# Shield.net
KiCad netlist of a schematic drawn in EAGLE
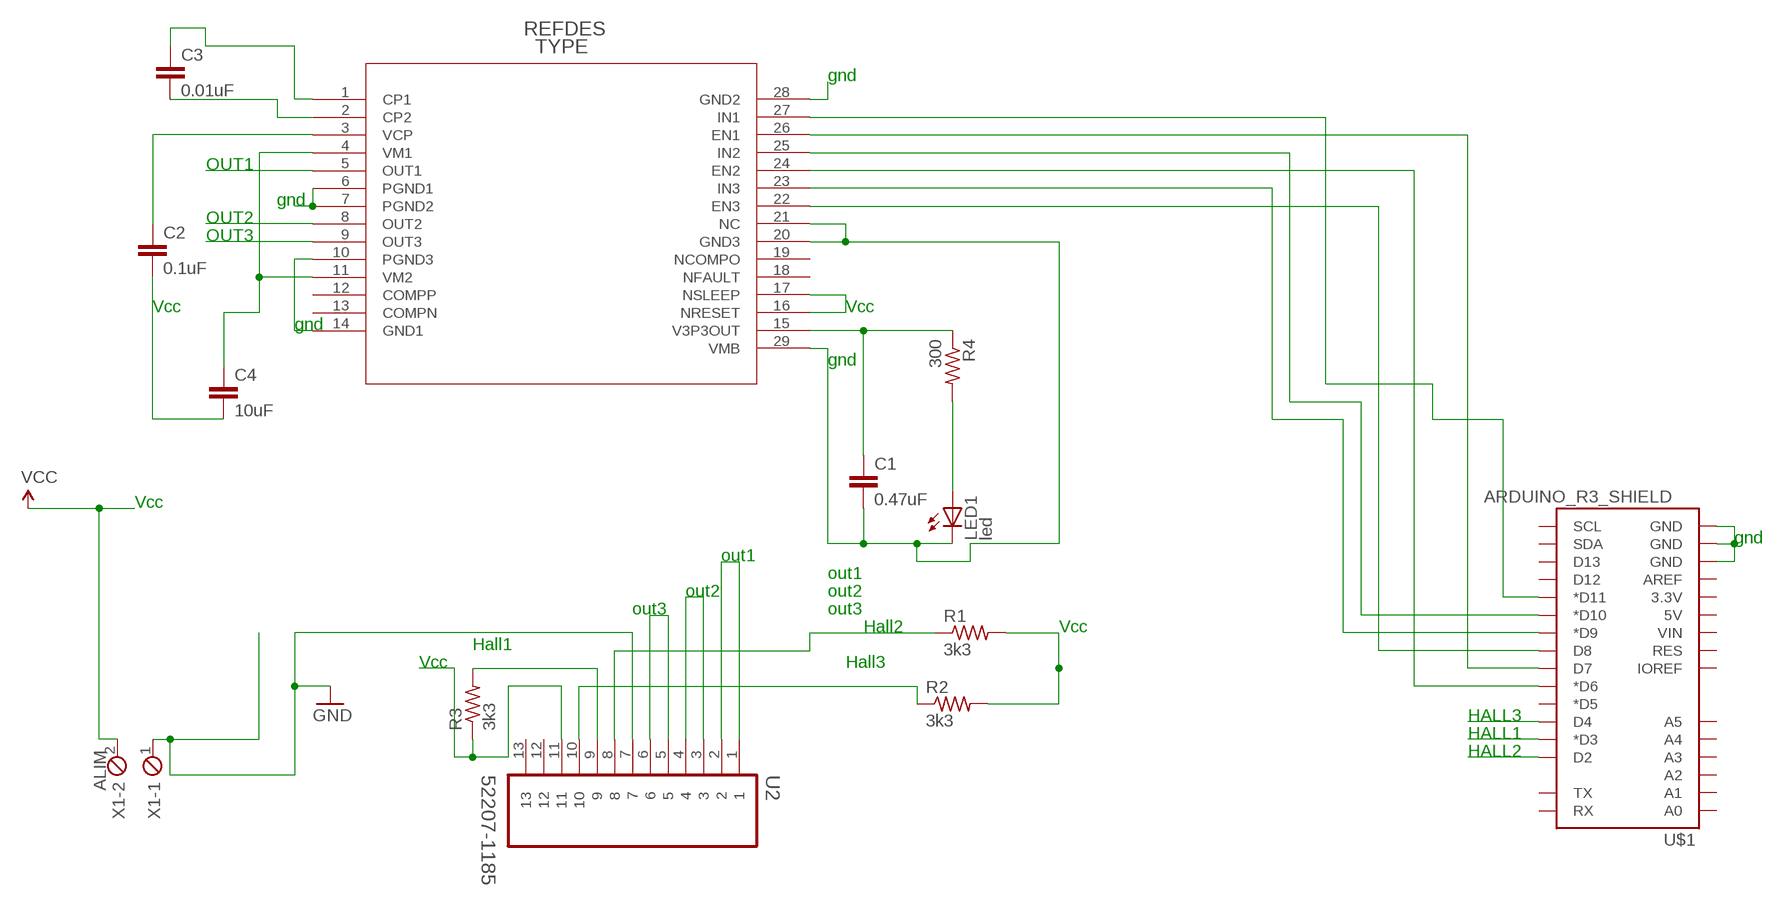
[diagram p0: schematic, sheet 1]

(export (version "E")
  (design (tool "Eeschema 10.0.6"))
  (components
    (comp (ref "C1")
      (value "0.47uF")
      (footprint "eagle-import:C025-025X050")
      (libsource (lib "eagle-import") (part "C-EU025-025X050"))
    )
    (comp (ref "C2")
      (value "0.1uF")
      (footprint "eagle-import:C102-043X133")
      (libsource (lib "eagle-import") (part "C-EU102-043X133"))
    )
    (comp (ref "C3")
      (value "0.01uF")
      (footprint "eagle-import:C025-025X050")
      (libsource (lib "eagle-import") (part "C-EU025-025X050"))
    )
    (comp (ref "C4")
      (value "10uF")
      (footprint "eagle-import:C025-050X050")
      (libsource (lib "eagle-import") (part "C-EU025-050X050"))
    )
    (comp (ref "LED1")
      (value "led")
      (footprint "eagle-import:LED3MM")
      (libsource (lib "eagle-import") (part "LED3MM"))
    )
    (comp (ref "R1")
      (value "3k3")
      (footprint "eagle-import:0207_10")
      (libsource (lib "eagle-import") (part "R-US_0207/10"))
    )
    (comp (ref "R2")
      (value "3k3")
      (footprint "eagle-import:0207_10")
      (libsource (lib "eagle-import") (part "R-US_0207/10"))
    )
    (comp (ref "R3")
      (value "3k3")
      (footprint "eagle-import:0207_10")
      (libsource (lib "eagle-import") (part "R-US_0207/10"))
    )
    (comp (ref "R4")
      (value "300")
      (footprint "eagle-import:0207_10")
      (libsource (lib "eagle-import") (part "R-US_0207/10"))
    )
    (comp (ref "U$1")
      (value "ARDUINO_R3_SHIELD")
      (footprint "eagle-import:UNO_R3_SHIELD")
      (libsource (lib "eagle-import") (part "ARDUINO_R3_SHIELD"))
    )
    (comp (ref "U1")
      (value "DRV8811_PWP_28")
      (footprint "eagle-import:PWP28_5P18X3P1")
      (libsource (lib "eagle-import") (part "DRV8811_PWP_28"))
    )
    (comp (ref "U2")
      (value "52207-1185")
      (footprint "eagle-import:MOLEX_52207-1185")
      (fields (field (name "MPN") "52207-1085"))
      (libsource (lib "eagle-import") (part "52207-1185"))
    )
    (comp (ref "X1")
      (value "ALIM")
      (footprint "eagle-import:2POL254")
      (libsource (lib "eagle-import") (part "MPT2"))
    )
  )
  (nets
    (net (code "1") (name "/HALL1") (class "Default")
      (node (ref "R3") (pin "2") (pinfunction "2_2") (pintype "passive"))
      (node (ref "U$1") (pin "D3") (pinfunction "*D3_D3") (pintype "bidirectional"))
      (node (ref "U2") (pin "9") (pinfunction "9_9") (pintype "passive"))
    )
    (net (code "2") (name "/HALL2") (class "Default")
      (node (ref "R1") (pin "1") (pinfunction "1_1") (pintype "passive"))
      (node (ref "U$1") (pin "D2") (pinfunction "D2_D2") (pintype "bidirectional"))
      (node (ref "U2") (pin "8") (pinfunction "8_8") (pintype "passive"))
    )
    (net (code "3") (name "/HALL3") (class "Default")
      (node (ref "R2") (pin "1") (pinfunction "1_1") (pintype "passive"))
      (node (ref "U$1") (pin "D4") (pinfunction "D4_D4") (pintype "bidirectional"))
      (node (ref "U2") (pin "10") (pinfunction "10_10") (pintype "passive"))
    )
    (net (code "4") (name "/OUT1") (class "Default")
      (node (ref "U1") (pin "5") (pinfunction "OUT1_5") (pintype "passive"))
      (node (ref "U2") (pin "1") (pinfunction "1_1") (pintype "passive"))
      (node (ref "U2") (pin "2") (pinfunction "2_2") (pintype "passive"))
    )
    (net (code "5") (name "/OUT2") (class "Default")
      (node (ref "U1") (pin "8") (pinfunction "OUT2_8") (pintype "passive"))
      (node (ref "U2") (pin "3") (pinfunction "3_3") (pintype "passive"))
      (node (ref "U2") (pin "4") (pinfunction "4_4") (pintype "passive"))
    )
    (net (code "6") (name "/OUT3") (class "Default")
      (node (ref "U1") (pin "9") (pinfunction "OUT3_9") (pintype "passive"))
      (node (ref "U2") (pin "5") (pinfunction "5_5") (pintype "passive"))
      (node (ref "U2") (pin "6") (pinfunction "6_6") (pintype "passive"))
    )
    (net (code "7") (name "GND") (class "Default")
      (node (ref "C1") (pin "2") (pinfunction "2_2") (pintype "passive"))
      (node (ref "LED1") (pin "K") (pinfunction "C_K") (pintype "passive"))
      (node (ref "U$1") (pin "GND@0") (pinfunction "GND_GND@0") (pintype "bidirectional"))
      (node (ref "U$1") (pin "GND@1") (pinfunction "GND_GND@1") (pintype "bidirectional"))
      (node (ref "U$1") (pin "GND@2") (pinfunction "GND_GND@2") (pintype "bidirectional"))
      (node (ref "U1") (pin "10") (pinfunction "PGND3_10") (pintype "passive"))
      (node (ref "U1") (pin "14") (pinfunction "GND1_14") (pintype "passive"))
      (node (ref "U1") (pin "20") (pinfunction "GND3_20") (pintype "passive"))
      (node (ref "U1") (pin "21") (pinfunction "NC_21") (pintype "passive"))
      (node (ref "U1") (pin "28") (pinfunction "GND2_28") (pintype "passive"))
      (node (ref "U1") (pin "29") (pinfunction "VMB_29") (pintype "passive"))
      (node (ref "U1") (pin "6") (pinfunction "PGND1_6") (pintype "passive"))
      (node (ref "U1") (pin "7") (pinfunction "PGND2_7") (pintype "passive"))
      (node (ref "U2") (pin "7") (pinfunction "7_7") (pintype "passive"))
      (node (ref "X1") (pin "1") (pinfunction "1_1") (pintype "passive"))
    )
    (net (code "8") (name "Net-(LED1-PadA)") (class "Default")
      (node (ref "LED1") (pin "A") (pinfunction "A_A") (pintype "passive"))
      (node (ref "R4") (pin "2") (pinfunction "2_2") (pintype "passive"))
    )
    (net (code "9") (name "Net-(U$1-*D6)") (class "Default")
      (node (ref "U$1") (pin "D6") (pinfunction "*D6_D6") (pintype "bidirectional"))
      (node (ref "U1") (pin "24") (pinfunction "EN2_24") (pintype "passive"))
    )
    (net (code "10") (name "Net-(U$1-*D9)") (class "Default")
      (node (ref "U$1") (pin "D9") (pinfunction "*D9_D9") (pintype "bidirectional"))
      (node (ref "U1") (pin "23") (pinfunction "IN3_23") (pintype "passive"))
    )
    (net (code "11") (name "Net-(U$1-*D10)") (class "Default")
      (node (ref "U$1") (pin "D10") (pinfunction "*D10_D10") (pintype "bidirectional"))
      (node (ref "U1") (pin "25") (pinfunction "IN2_25") (pintype "passive"))
    )
    (net (code "12") (name "Net-(U$1-*D11)") (class "Default")
      (node (ref "U$1") (pin "D11") (pinfunction "*D11_D11") (pintype "bidirectional"))
      (node (ref "U1") (pin "27") (pinfunction "IN1_27") (pintype "passive"))
    )
    (net (code "13") (name "Net-(U1-CP1)") (class "Default")
      (node (ref "C3") (pin "1") (pinfunction "1_1") (pintype "passive"))
      (node (ref "U1") (pin "1") (pinfunction "CP1_1") (pintype "passive"))
    )
    (net (code "14") (name "Net-(U1-CP2)") (class "Default")
      (node (ref "C3") (pin "2") (pinfunction "2_2") (pintype "passive"))
      (node (ref "U1") (pin "2") (pinfunction "CP2_2") (pintype "passive"))
    )
    (net (code "15") (name "Net-(U1-EN1)") (class "Default")
      (node (ref "U$1") (pin "D7") (pinfunction "D7_D7") (pintype "bidirectional"))
      (node (ref "U1") (pin "26") (pinfunction "EN1_26") (pintype "passive"))
    )
    (net (code "16") (name "Net-(U1-EN3)") (class "Default")
      (node (ref "U$1") (pin "D8") (pinfunction "D8_D8") (pintype "bidirectional"))
      (node (ref "U1") (pin "22") (pinfunction "EN3_22") (pintype "passive"))
    )
    (net (code "17") (name "Net-(U1-V3P3OUT)") (class "Default")
      (node (ref "C1") (pin "1") (pinfunction "1_1") (pintype "passive"))
      (node (ref "R4") (pin "1") (pinfunction "1_1") (pintype "passive"))
      (node (ref "U1") (pin "15") (pinfunction "V3P3OUT_15") (pintype "passive"))
    )
    (net (code "18") (name "Net-(U1-VCP)") (class "Default")
      (node (ref "C2") (pin "1") (pinfunction "1_1") (pintype "passive"))
      (node (ref "U1") (pin "3") (pinfunction "VCP_3") (pintype "passive"))
    )
    (net (code "19") (name "Net-(U1-VM1)") (class "Default")
      (node (ref "C4") (pin "1") (pinfunction "1_1") (pintype "passive"))
      (node (ref "U1") (pin "11") (pinfunction "VM2_11") (pintype "passive"))
      (node (ref "U1") (pin "4") (pinfunction "VM1_4") (pintype "passive"))
    )
    (net (code "20") (name "VCC") (class "Default")
      (node (ref "C2") (pin "2") (pinfunction "2_2") (pintype "passive"))
      (node (ref "C4") (pin "2") (pinfunction "2_2") (pintype "passive"))
      (node (ref "R1") (pin "2") (pinfunction "2_2") (pintype "passive"))
      (node (ref "R2") (pin "2") (pinfunction "2_2") (pintype "passive"))
      (node (ref "R3") (pin "1") (pinfunction "1_1") (pintype "passive"))
      (node (ref "U1") (pin "16") (pinfunction "NRESET_16") (pintype "passive"))
      (node (ref "U1") (pin "17") (pinfunction "NSLEEP_17") (pintype "passive"))
      (node (ref "U2") (pin "11") (pinfunction "11_11") (pintype "passive"))
      (node (ref "X1") (pin "2") (pinfunction "1_2") (pintype "passive"))
    )
    (net (code "21") (name "unconnected-(U$1-*D5-PadD5)") (class "Default")
      (node (ref "U$1") (pin "D5") (pinfunction "*D5_D5") (pintype "bidirectional"))
    )
    (net (code "22") (name "unconnected-(U$1-Pad3.3V)") (class "Default")
      (node (ref "U$1") (pin "3.3V") (pinfunction "3.3V_3.3V") (pintype "bidirectional"))
    )
    (net (code "23") (name "unconnected-(U$1-Pad5V)") (class "Default")
      (node (ref "U$1") (pin "5V") (pinfunction "5V_5V") (pintype "bidirectional"))
    )
    (net (code "24") (name "unconnected-(U$1-PadA0)") (class "Default")
      (node (ref "U$1") (pin "A0") (pinfunction "A0_A0") (pintype "bidirectional"))
    )
    (net (code "25") (name "unconnected-(U$1-PadA1)") (class "Default")
      (node (ref "U$1") (pin "A1") (pinfunction "A1_A1") (pintype "bidirectional"))
    )
    (net (code "26") (name "unconnected-(U$1-PadA2)") (class "Default")
      (node (ref "U$1") (pin "A2") (pinfunction "A2_A2") (pintype "bidirectional"))
    )
    (net (code "27") (name "unconnected-(U$1-PadA3)") (class "Default")
      (node (ref "U$1") (pin "A3") (pinfunction "A3_A3") (pintype "bidirectional"))
    )
    (net (code "28") (name "unconnected-(U$1-PadA4)") (class "Default")
      (node (ref "U$1") (pin "A4") (pinfunction "A4_A4") (pintype "bidirectional"))
    )
    (net (code "29") (name "unconnected-(U$1-PadA5)") (class "Default")
      (node (ref "U$1") (pin "A5") (pinfunction "A5_A5") (pintype "bidirectional"))
    )
    (net (code "30") (name "unconnected-(U$1-PadAREF)") (class "Default")
      (node (ref "U$1") (pin "AREF") (pinfunction "AREF_AREF") (pintype "bidirectional"))
    )
    (net (code "31") (name "unconnected-(U$1-PadD12)") (class "Default")
      (node (ref "U$1") (pin "D12") (pinfunction "D12_D12") (pintype "bidirectional"))
    )
    (net (code "32") (name "unconnected-(U$1-PadD13)") (class "Default")
      (node (ref "U$1") (pin "D13") (pinfunction "D13_D13") (pintype "bidirectional"))
    )
    (net (code "33") (name "unconnected-(U$1-PadIOREF)") (class "Default")
      (node (ref "U$1") (pin "IOREF") (pinfunction "IOREF_IOREF") (pintype "bidirectional"))
    )
    (net (code "34") (name "unconnected-(U$1-PadRES)") (class "Default")
      (node (ref "U$1") (pin "RES") (pinfunction "RES_RES") (pintype "bidirectional"))
    )
    (net (code "35") (name "unconnected-(U$1-PadRX)") (class "Default")
      (node (ref "U$1") (pin "RX") (pinfunction "RX_RX") (pintype "bidirectional"))
    )
    (net (code "36") (name "unconnected-(U$1-PadSCL)") (class "Default")
      (node (ref "U$1") (pin "SCL") (pinfunction "SCL_SCL") (pintype "bidirectional"))
    )
    (net (code "37") (name "unconnected-(U$1-PadSDA)") (class "Default")
      (node (ref "U$1") (pin "SDA") (pinfunction "SDA_SDA") (pintype "bidirectional"))
    )
    (net (code "38") (name "unconnected-(U$1-PadTX)") (class "Default")
      (node (ref "U$1") (pin "TX") (pinfunction "TX_TX") (pintype "bidirectional"))
    )
    (net (code "39") (name "unconnected-(U$1-PadVIN)") (class "Default")
      (node (ref "U$1") (pin "VIN") (pinfunction "VIN_VIN") (pintype "bidirectional"))
    )
    (net (code "40") (name "unconnected-(U1-COMPN-Pad13)") (class "Default")
      (node (ref "U1") (pin "13") (pinfunction "COMPN_13") (pintype "passive"))
    )
    (net (code "41") (name "unconnected-(U1-COMPP-Pad12)") (class "Default")
      (node (ref "U1") (pin "12") (pinfunction "COMPP_12") (pintype "passive"))
    )
    (net (code "42") (name "unconnected-(U1-NCOMPO-Pad19)") (class "Default")
      (node (ref "U1") (pin "19") (pinfunction "NCOMPO_19") (pintype "passive"))
    )
    (net (code "43") (name "unconnected-(U1-NFAULT-Pad18)") (class "Default")
      (node (ref "U1") (pin "18") (pinfunction "NFAULT_18") (pintype "passive"))
    )
    (net (code "44") (name "unconnected-(U2-Pad12)") (class "Default")
      (node (ref "U2") (pin "12") (pinfunction "12_12") (pintype "passive"))
    )
    (net (code "45") (name "unconnected-(U2-Pad13)") (class "Default")
      (node (ref "U2") (pin "13") (pinfunction "13_13") (pintype "passive"))
    )
  )
)
